# Apollo_ES_Board.net
KiCad netlist of a schematic drawn in Altium Designer
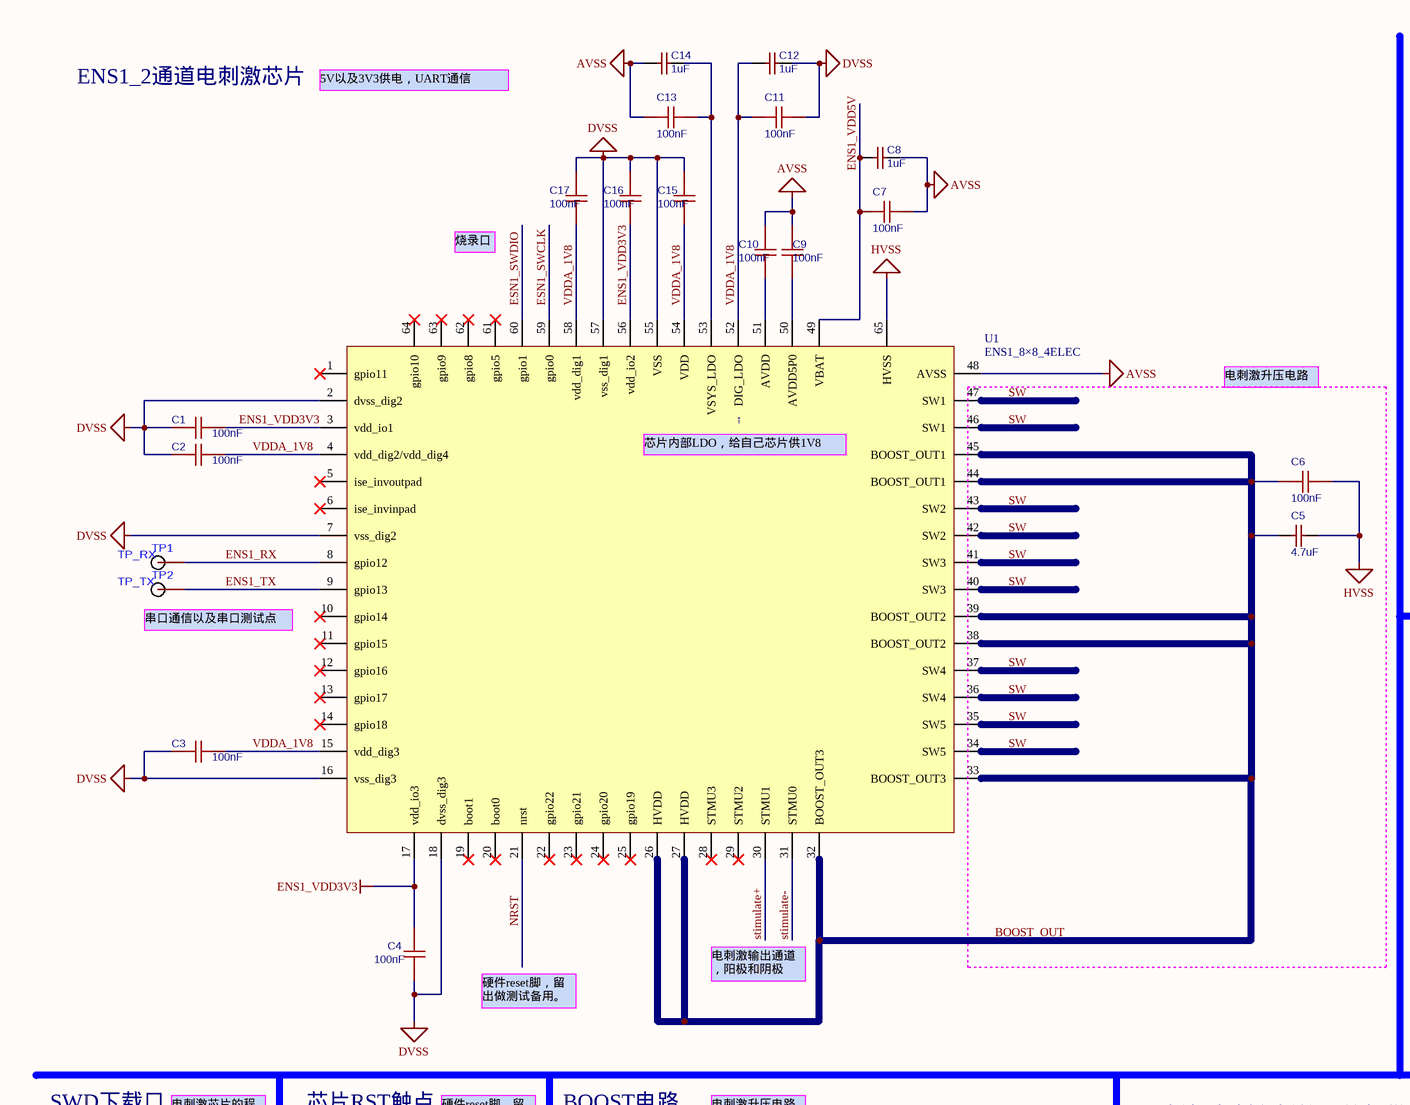
[diagram p0: Apollo_ES_Board.SchDoc, top left]
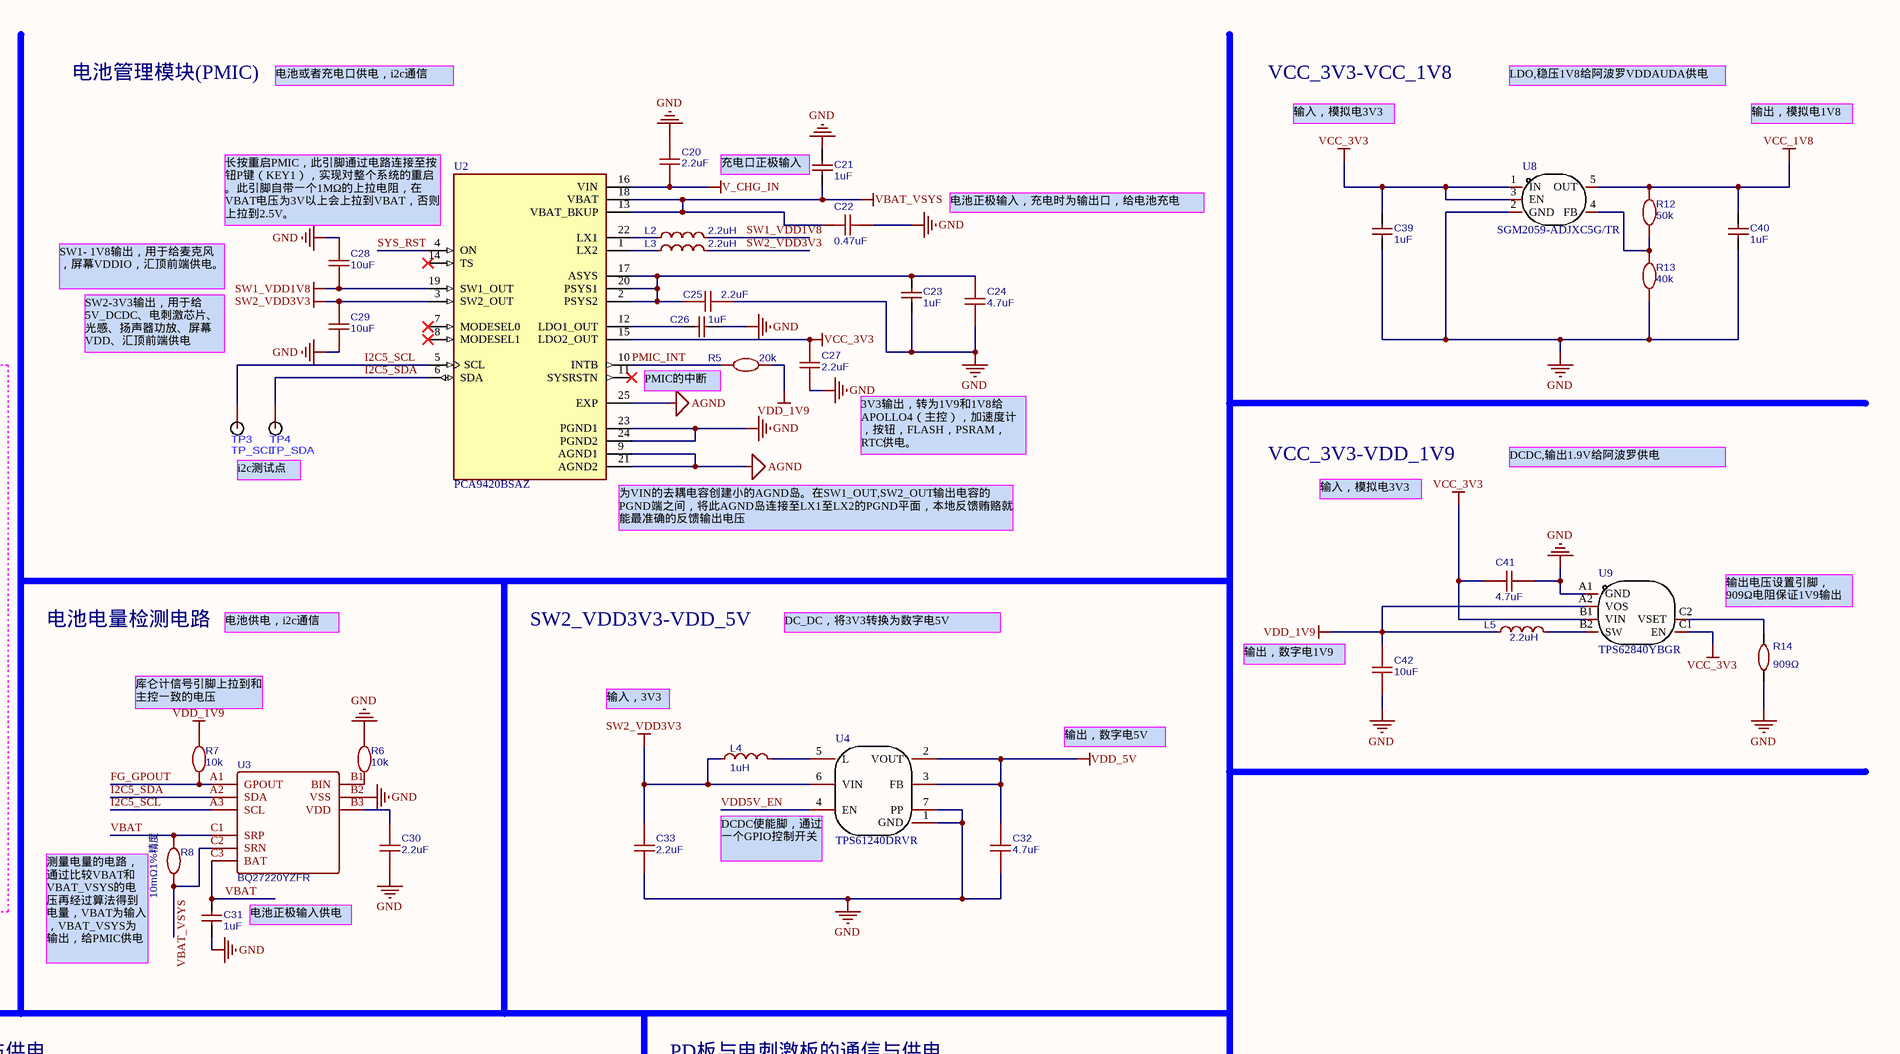
[diagram p1: Apollo_ES_Board.SchDoc, top right]
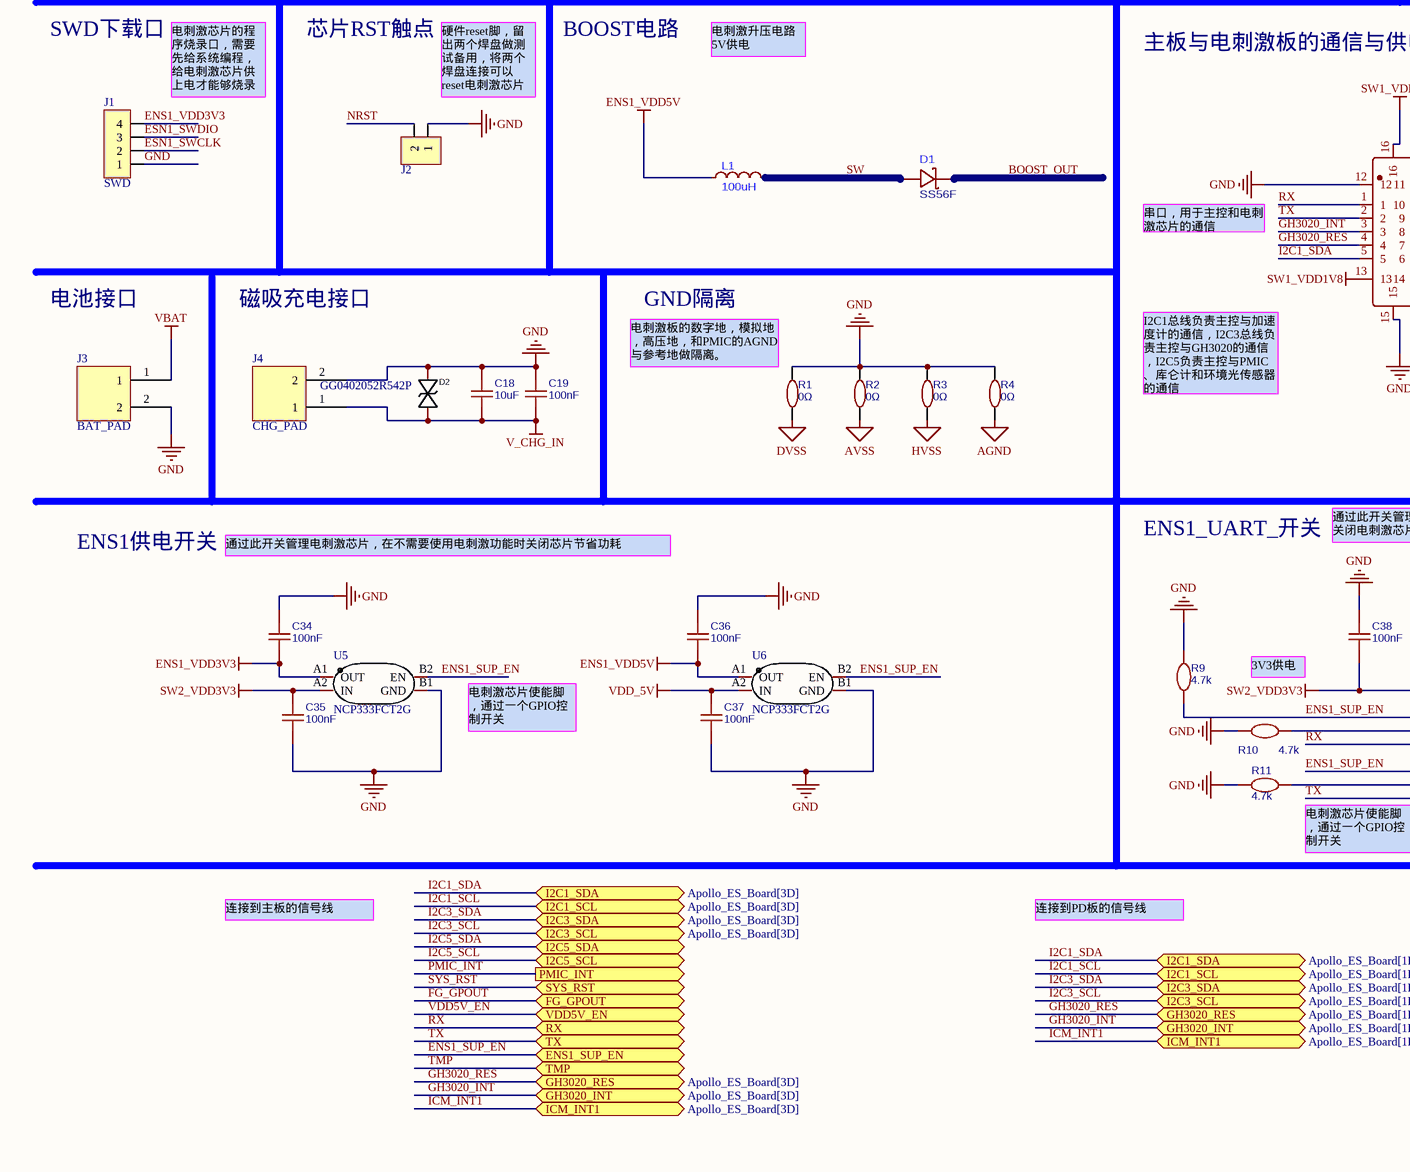
[diagram p2: Apollo_ES_Board.SchDoc, bottom left]
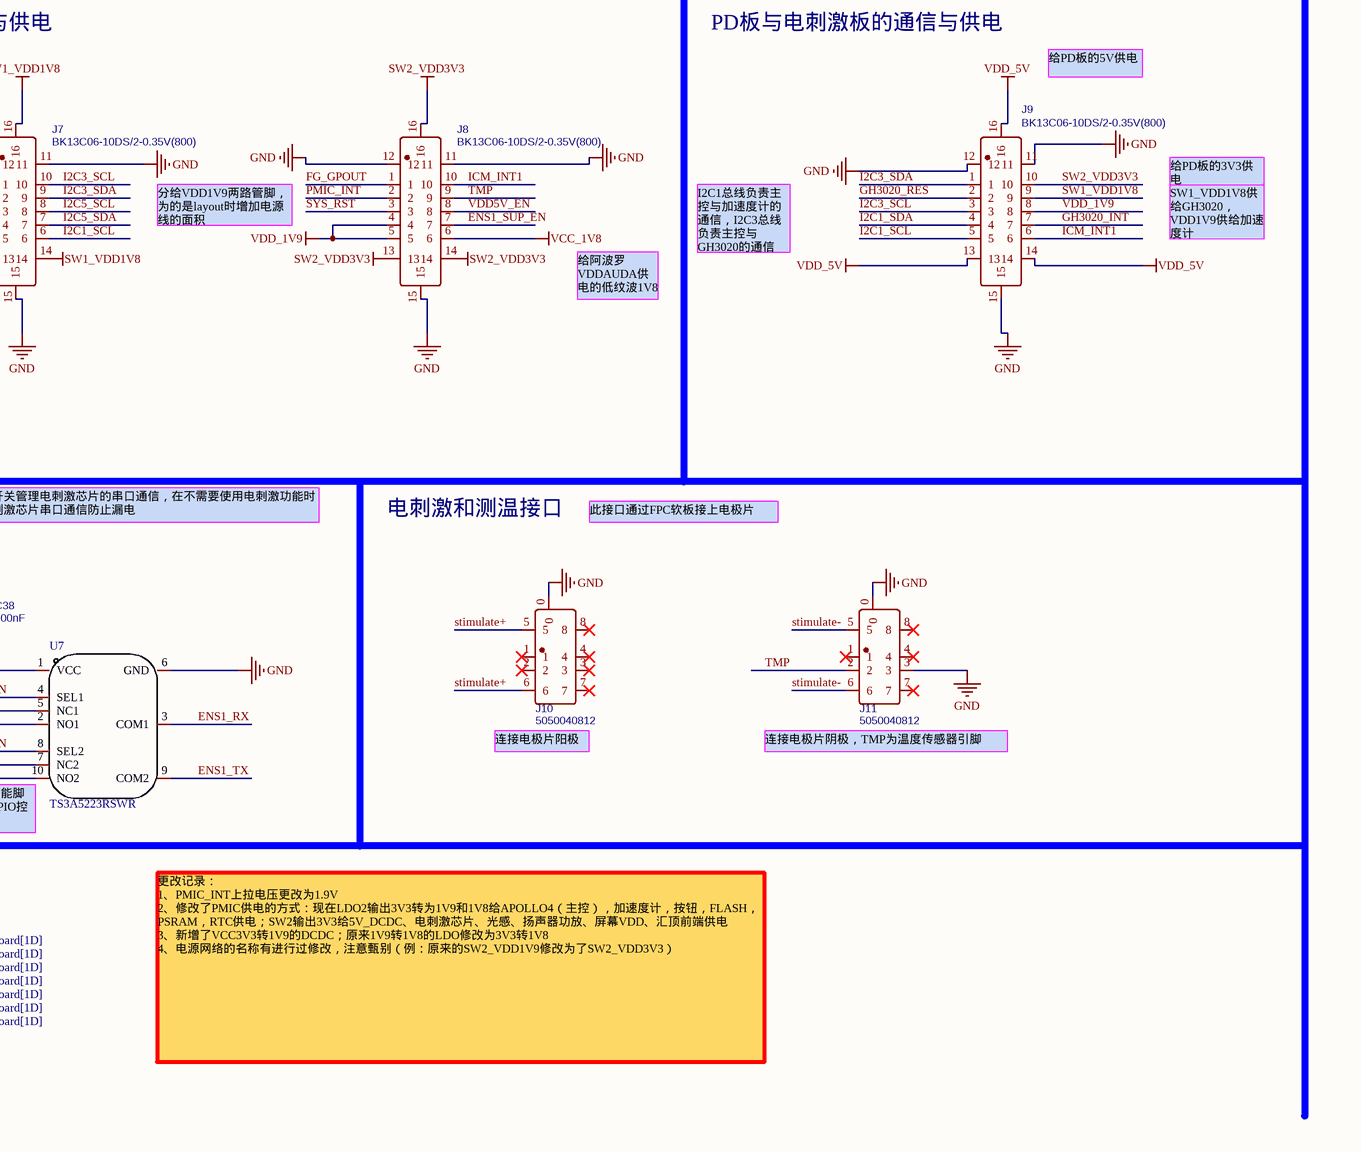
[diagram p3: Apollo_ES_Board.SchDoc, bottom right]

(export (version "E")
  (design (tool "Eeschema 10.0.6"))
  (components
    (comp (ref "C1")
      (value "100nF")
      (footprint "smart bracelet:C0201")
      (description "CL03A104KO3NNNC\r\n额定电压: 16V\r\n材质(温度系数): X5R")
      (fields
        (field (name "BOM_MANUFACTURER PART") "CL10B104KB8NNNC")
        (field (name "BOM_SUPPLIER PART") "C1591")
      )
      (libsource (lib "smart bracelet") (part "100nF"))
    )
    (comp (ref "C2")
      (value "100nF")
      (footprint "smart bracelet:C0201")
      (description "CL03A104KO3NNNC\r\n额定电压: 16V\r\n材质(温度系数): X5R")
      (fields
        (field (name "BOM_MANUFACTURER PART") "CL10B104KB8NNNC")
        (field (name "BOM_SUPPLIER PART") "C1591")
      )
      (libsource (lib "smart bracelet") (part "100nF"))
    )
    (comp (ref "C3")
      (value "100nF")
      (footprint "smart bracelet:C0201")
      (description "CL03A104KO3NNNC\r\n额定电压: 16V\r\n材质(温度系数): X5R")
      (fields
        (field (name "BOM_MANUFACTURER PART") "CL10B104KB8NNNC")
        (field (name "BOM_SUPPLIER PART") "C1591")
      )
      (libsource (lib "smart bracelet") (part "100nF"))
    )
    (comp (ref "C4")
      (value "100nF")
      (footprint "smart bracelet:C0201")
      (description "CL03A104KO3NNNC\r\n额定电压: 16V\r\n材质(温度系数): X5R")
      (fields
        (field (name "BOM_MANUFACTURER PART") "CL10B104KB8NNNC")
        (field (name "BOM_SUPPLIER PART") "C1591")
      )
      (libsource (lib "smart bracelet") (part "100nF"))
    )
    (comp (ref "C5")
      (value "4.7uF")
      (footprint "C1206")
      (fields
        (field (name "BOM_MANUFACTURER PART") "CL10A105KB8NNNC")
        (field (name "BOM_SUPPLIER PART") "C15849")
      )
      (libsource (lib "smart bracelet") (part "1uF"))
    )
    (comp (ref "C6")
      (value "100nF")
      (footprint "smart bracelet:C0805")
      (fields
        (field (name "BOM_MANUFACTURER PART") "CL10B104KB8NNNC")
        (field (name "BOM_SUPPLIER PART") "C1591")
      )
      (libsource (lib "smart bracelet") (part "100nF"))
    )
    (comp (ref "C7")
      (value "100nF")
      (footprint "smart bracelet:C0201")
      (description "CL03A104KO3NNNC\r\n额定电压: 16V\r\n材质(温度系数): X5R")
      (fields
        (field (name "BOM_MANUFACTURER PART") "CL10B104KB8NNNC")
        (field (name "BOM_SUPPLIER PART") "C1591")
      )
      (libsource (lib "smart bracelet") (part "100nF"))
    )
    (comp (ref "C8")
      (value "1uF")
      (footprint "C0201")
      (description "GRM033R61A105ME44D\r\n精度: ±20%\r\n额定电压: 10V\r\n材质(温度系数): X5R")
      (fields
        (field (name "BOM_MANUFACTURER PART") "CL10A105KB8NNNC")
        (field (name "BOM_SUPPLIER PART") "C15849")
      )
      (libsource (lib "smart bracelet") (part "1uF"))
    )
    (comp (ref "C9")
      (value "100nF")
      (footprint "smart bracelet:C0201")
      (description "CL03A104KO3NNNC\r\n额定电压: 16V\r\n材质(温度系数): X5R")
      (fields
        (field (name "BOM_MANUFACTURER PART") "CL10B104KB8NNNC")
        (field (name "BOM_SUPPLIER PART") "C1591")
      )
      (libsource (lib "smart bracelet") (part "100nF"))
    )
    (comp (ref "C10")
      (value "100nF")
      (footprint "smart bracelet:C0201")
      (description "CL03A104KO3NNNC\r\n额定电压: 16V\r\n材质(温度系数): X5R")
      (fields
        (field (name "BOM_MANUFACTURER PART") "CL10B104KB8NNNC")
        (field (name "BOM_SUPPLIER PART") "C1591")
      )
      (libsource (lib "smart bracelet") (part "100nF"))
    )
    (comp (ref "C11")
      (value "100nF")
      (footprint "smart bracelet:C0201")
      (description "CL03A104KO3NNNC\r\n额定电压: 16V\r\n材质(温度系数): X5R")
      (fields
        (field (name "BOM_MANUFACTURER PART") "CL10B104KB8NNNC")
        (field (name "BOM_SUPPLIER PART") "C1591")
      )
      (libsource (lib "smart bracelet") (part "100nF"))
    )
    (comp (ref "C12")
      (value "1uF")
      (footprint "C0201")
      (description "GRM033R61A105ME44D\r\n精度: ±20%\r\n额定电压: 10V\r\n材质(温度系数): X5R")
      (fields
        (field (name "BOM_MANUFACTURER PART") "CL10A105KB8NNNC")
        (field (name "BOM_SUPPLIER PART") "C15849")
      )
      (libsource (lib "smart bracelet") (part "1uF"))
    )
    (comp (ref "C13")
      (value "100nF")
      (footprint "smart bracelet:C0201")
      (description "CL03A104KO3NNNC\r\n额定电压: 16V\r\n材质(温度系数): X5R")
      (fields
        (field (name "BOM_MANUFACTURER PART") "CL10B104KB8NNNC")
        (field (name "BOM_SUPPLIER PART") "C1591")
      )
      (libsource (lib "smart bracelet") (part "100nF"))
    )
    (comp (ref "C14")
      (value "1uF")
      (footprint "C0201")
      (description "GRM033R61A105ME44D\r\n精度: ±20%\r\n额定电压: 10V\r\n材质(温度系数): X5R")
      (fields
        (field (name "BOM_MANUFACTURER PART") "CL10A105KB8NNNC")
        (field (name "BOM_SUPPLIER PART") "C15849")
      )
      (libsource (lib "smart bracelet") (part "1uF"))
    )
    (comp (ref "C15")
      (value "100nF")
      (footprint "smart bracelet:C0201")
      (description "CL03A104KO3NNNC\r\n额定电压: 16V\r\n材质(温度系数): X5R")
      (fields
        (field (name "BOM_MANUFACTURER PART") "CL10B104KB8NNNC")
        (field (name "BOM_SUPPLIER PART") "C1591")
      )
      (libsource (lib "smart bracelet") (part "100nF"))
    )
    (comp (ref "C16")
      (value "100nF")
      (footprint "smart bracelet:C0201")
      (description "CL03A104KO3NNNC\r\n额定电压: 16V\r\n材质(温度系数): X5R")
      (fields
        (field (name "BOM_MANUFACTURER PART") "CL10B104KB8NNNC")
        (field (name "BOM_SUPPLIER PART") "C1591")
      )
      (libsource (lib "smart bracelet") (part "100nF"))
    )
    (comp (ref "C17")
      (value "100nF")
      (footprint "smart bracelet:C0201")
      (description "CL03A104KO3NNNC\r\n额定电压: 16V\r\n材质(温度系数): X5R")
      (fields
        (field (name "BOM_MANUFACTURER PART") "CL10B104KB8NNNC")
        (field (name "BOM_SUPPLIER PART") "C1591")
      )
      (libsource (lib "smart bracelet") (part "100nF"))
    )
    (comp (ref "C18")
      (value "10uF")
      (footprint "smart bracelet:C0402")
      (description "CL05A106MQ5NUNC\r\n精度: ±20%\r\n额定电压: 6.3V\r\n材质(温度系数): X5R")
      (fields
        (field (name "BOM_SUPPLIER PART") "C2932476")
        (field (name "BOM_MANUFACTURER PART") "CL21A106KBYQNNE")
        (field (name "CONTRIBUTOR") "lcsc")
      )
      (libsource (lib "smart bracelet") (part "10uF"))
    )
    (comp (ref "C19")
      (value "100nF")
      (footprint "smart bracelet:C0201")
      (description "CL03A104KO3NNNC\r\n额定电压: 16V\r\n材质(温度系数): X5R")
      (fields
        (field (name "BOM_MANUFACTURER PART") "CL10B104KB8NNNC")
        (field (name "BOM_SUPPLIER PART") "C1591")
      )
      (libsource (lib "smart bracelet") (part "100nF"))
    )
    (comp (ref "C20")
      (value "2.2uF")
      (footprint "smart bracelet:C0201")
      (fields
        (field (name "BOM_SUPPLIER PART") "C913904")
        (field (name "BOM_MANUFACTURER PART") "CL10A225KB8NNNC")
        (field (name "CONTRIBUTOR") "LCSC")
      )
      (libsource (lib "smart bracelet") (part "C0201"))
    )
    (comp (ref "C21")
      (value "1uF")
      (footprint "C0201")
      (description "GRM033R61A105ME44D\r\n精度: ±20%\r\n额定电压: 10V\r\n材质(温度系数): X5R")
      (fields
        (field (name "BOM_MANUFACTURER PART") "CL10A105KB8NNNC")
        (field (name "BOM_SUPPLIER PART") "C15849")
      )
      (libsource (lib "smart bracelet") (part "1uF"))
    )
    (comp (ref "C22")
      (value "0.47uF")
      (footprint "smart bracelet:C0201")
      (fields
        (field (name "BOM_SUPPLIER PART") "C913904")
        (field (name "BOM_MANUFACTURER PART") "CL10A225KB8NNNC")
        (field (name "CONTRIBUTOR") "LCSC")
      )
      (libsource (lib "smart bracelet") (part "C0201"))
    )
    (comp (ref "C23")
      (value "1uF")
      (footprint "C0201")
      (description "GRM033R61A105ME44D\r\n精度: ±20%\r\n额定电压: 10V\r\n材质(温度系数): X5R")
      (fields
        (field (name "BOM_MANUFACTURER PART") "CL10A105KB8NNNC")
        (field (name "BOM_SUPPLIER PART") "C15849")
      )
      (libsource (lib "smart bracelet") (part "1uF"))
    )
    (comp (ref "C24")
      (value "4.7uF")
      (footprint "C0201")
      (fields
        (field (name "BOM_SUPPLIER PART") "C237304")
        (field (name "BOM_MANUFACTURER PART") "GRM31CC72A475KE11L")
        (field (name "CONTRIBUTOR") "LCSC")
      )
      (libsource (lib "smart bracelet") (part "4.7uF"))
    )
    (comp (ref "C25")
      (value "2.2uF")
      (footprint "smart bracelet:C0201")
      (fields
        (field (name "BOM_SUPPLIER PART") "C913904")
        (field (name "BOM_MANUFACTURER PART") "CL10A225KB8NNNC")
        (field (name "CONTRIBUTOR") "LCSC")
      )
      (libsource (lib "smart bracelet") (part "C0201"))
    )
    (comp (ref "C26")
      (value "1uF")
      (footprint "C0201")
      (description "GRM033R61A105ME44D\r\n精度: ±20%\r\n额定电压: 10V\r\n材质(温度系数): X5R")
      (fields
        (field (name "BOM_MANUFACTURER PART") "CL10A105KB8NNNC")
        (field (name "BOM_SUPPLIER PART") "C15849")
      )
      (libsource (lib "smart bracelet") (part "1uF"))
    )
    (comp (ref "C27")
      (value "2.2uF")
      (footprint "smart bracelet:C0201")
      (fields
        (field (name "BOM_SUPPLIER PART") "C913904")
        (field (name "BOM_MANUFACTURER PART") "CL10A225KB8NNNC")
        (field (name "CONTRIBUTOR") "LCSC")
      )
      (libsource (lib "smart bracelet") (part "C0201"))
    )
    (comp (ref "C28")
      (value "10uF")
      (footprint "smart bracelet:C0402")
      (fields
        (field (name "BOM_SUPPLIER PART") "C913904")
        (field (name "BOM_MANUFACTURER PART") "CL10A225KB8NNNC")
        (field (name "CONTRIBUTOR") "LCSC")
      )
      (libsource (lib "smart bracelet") (part "C0402"))
    )
    (comp (ref "C29")
      (value "10uF")
      (footprint "smart bracelet:C0402")
      (fields
        (field (name "BOM_SUPPLIER PART") "C913904")
        (field (name "BOM_MANUFACTURER PART") "CL10A225KB8NNNC")
        (field (name "CONTRIBUTOR") "LCSC")
      )
      (libsource (lib "smart bracelet") (part "C0402"))
    )
    (comp (ref "C30")
      (value "2.2uF")
      (footprint "smart bracelet:C0201")
      (fields
        (field (name "BOM_SUPPLIER PART") "C913904")
        (field (name "BOM_MANUFACTURER PART") "CL10A225KB8NNNC")
        (field (name "CONTRIBUTOR") "LCSC")
      )
      (libsource (lib "smart bracelet") (part "C0201"))
    )
    (comp (ref "C31")
      (value "1uF")
      (footprint "C0201")
      (description "GRM033R61A105ME44D\r\n精度: ±20%\r\n额定电压: 10V\r\n材质(温度系数): X5R")
      (fields
        (field (name "BOM_MANUFACTURER PART") "CL10A105KB8NNNC")
        (field (name "BOM_SUPPLIER PART") "C15849")
      )
      (libsource (lib "smart bracelet") (part "1uF"))
    )
    (comp (ref "C32")
      (value "4.7uF")
      (footprint "C0201")
      (fields
        (field (name "BOM_SUPPLIER PART") "C237304")
        (field (name "BOM_MANUFACTURER PART") "GRM31CC72A475KE11L")
        (field (name "CONTRIBUTOR") "LCSC")
      )
      (libsource (lib "smart bracelet") (part "4.7uF"))
    )
    (comp (ref "C33")
      (value "2.2uF")
      (footprint "smart bracelet:C0201")
      (fields
        (field (name "BOM_SUPPLIER PART") "C913904")
        (field (name "BOM_MANUFACTURER PART") "CL10A225KB8NNNC")
        (field (name "CONTRIBUTOR") "LCSC")
      )
      (libsource (lib "smart bracelet") (part "C0201"))
    )
    (comp (ref "C34")
      (value "100nF")
      (footprint "smart bracelet:C0201")
      (description "CL03A104KO3NNNC\r\n额定电压: 16V\r\n材质(温度系数): X5R")
      (fields
        (field (name "BOM_MANUFACTURER PART") "CL10B104KB8NNNC")
        (field (name "BOM_SUPPLIER PART") "C1591")
      )
      (libsource (lib "smart bracelet") (part "100nF"))
    )
    (comp (ref "C35")
      (value "100nF")
      (footprint "smart bracelet:C0201")
      (description "CL03A104KO3NNNC\r\n额定电压: 16V\r\n材质(温度系数): X5R")
      (fields
        (field (name "BOM_MANUFACTURER PART") "CL10B104KB8NNNC")
        (field (name "BOM_SUPPLIER PART") "C1591")
      )
      (libsource (lib "smart bracelet") (part "100nF"))
    )
    (comp (ref "C36")
      (value "100nF")
      (footprint "smart bracelet:C0201")
      (description "CL03A104KO3NNNC\r\n额定电压: 16V\r\n材质(温度系数): X5R")
      (fields
        (field (name "BOM_MANUFACTURER PART") "CL10B104KB8NNNC")
        (field (name "BOM_SUPPLIER PART") "C1591")
      )
      (libsource (lib "smart bracelet") (part "100nF"))
    )
    (comp (ref "C37")
      (value "100nF")
      (footprint "smart bracelet:C0201")
      (description "CL03A104KO3NNNC\r\n额定电压: 16V\r\n材质(温度系数): X5R")
      (fields
        (field (name "BOM_MANUFACTURER PART") "CL10B104KB8NNNC")
        (field (name "BOM_SUPPLIER PART") "C1591")
      )
      (libsource (lib "smart bracelet") (part "100nF"))
    )
    (comp (ref "C38")
      (value "100nF")
      (footprint "smart bracelet:C0201")
      (description "CL03A104KO3NNNC\r\n额定电压: 16V\r\n材质(温度系数): X5R")
      (fields
        (field (name "BOM_MANUFACTURER PART") "CL10B104KB8NNNC")
        (field (name "BOM_SUPPLIER PART") "C1591")
      )
      (libsource (lib "smart bracelet") (part "100nF"))
    )
    (comp (ref "C39")
      (value "1uF")
      (footprint "C0201")
      (description "GRM033R61A105ME44D\r\n精度: ±20%\r\n额定电压: 10V\r\n材质(温度系数): X5R")
      (fields
        (field (name "BOM_MANUFACTURER PART") "CL10A105KB8NNNC")
        (field (name "BOM_SUPPLIER PART") "C15849")
      )
      (libsource (lib "smart bracelet") (part "1uF"))
    )
    (comp (ref "C40")
      (value "1uF")
      (footprint "C0201")
      (description "GRM033R61A105ME44D\r\n精度: ±20%\r\n额定电压: 10V\r\n材质(温度系数): X5R")
      (fields
        (field (name "BOM_MANUFACTURER PART") "CL10A105KB8NNNC")
        (field (name "BOM_SUPPLIER PART") "C15849")
      )
      (libsource (lib "smart bracelet") (part "1uF"))
    )
    (comp (ref "C41")
      (value "4.7uF")
      (footprint "C0201")
      (fields
        (field (name "BOM_SUPPLIER PART") "C237304")
        (field (name "BOM_MANUFACTURER PART") "GRM31CC72A475KE11L")
        (field (name "CONTRIBUTOR") "LCSC")
      )
      (libsource (lib "smart bracelet") (part "4.7uF"))
    )
    (comp (ref "C42")
      (value "10uF")
      (footprint "smart bracelet:C0402")
      (fields
        (field (name "BOM_SUPPLIER PART") "C913904")
        (field (name "BOM_MANUFACTURER PART") "CL10A225KB8NNNC")
        (field (name "CONTRIBUTOR") "LCSC")
      )
      (libsource (lib "smart bracelet") (part "C0402"))
    )
    (comp (ref "D1")
      (value "SS56F")
      (footprint "SMAF_L3.5-W2.6-LS4.7-RD")
      (libsource (lib "altium-import") (part "root_2_SS56F_"))
    )
    (comp (ref "D2")
      (value "GG0402052R542P")
      (footprint "smart bracelet:0402")
      (fields (field (name "MANUFACTURER") "Kyocera AVX"))
      (libsource (lib "smart bracelet") (part "GG0402052R542P"))
    )
    (comp (ref "J1")
      (value "SWD")
      (footprint "4PIN_1.27mm")
      (description "Header, 4-Pin")
      (fields (field (name "PUBLISHER") "Altium Limited"))
      (libsource (lib "smart bracelet") (part "Header 4"))
    )
    (comp (ref "J2")
      (value "~")
      (footprint "2PIN_1.27mm")
      (description "Header, 2-Pin, encryption interface")
      (fields (field (name "PUBLISHER") "Altium Limited"))
      (libsource (lib "smart bracelet") (part "Header 2"))
    )
    (comp (ref "J3")
      (value "BAT_PAD")
      (footprint "MOTOR_PAD")
      (libsource (lib "smart bracelet") (part "MOTOR_PAD"))
    )
    (comp (ref "J4")
      (value "CHG_PAD")
      (footprint "CHG_PAD")
      (libsource (lib "smart bracelet") (part "CHG_PAD"))
    )
    (comp (ref "J7")
      (value "BK13C06-10DS/2-0.35V(800)")
      (footprint "smart bracelet:CONN-SMD_BK13C06-10DS-2-0.35V-800")
      (fields (field (name "MANUFACTURER") "HRS(广濑)") (field (name "CONTRIBUTOR") "lcsc"))
      (libsource (lib "smart bracelet") (part "10pin_ds_BK13C06-10DS/2-0.35V(800)"))
    )
    (comp (ref "J8")
      (value "BK13C06-10DS/2-0.35V(800)")
      (footprint "smart bracelet:CONN-SMD_BK13C06-10DS-2-0.35V-800")
      (fields (field (name "MANUFACTURER") "HRS(广濑)") (field (name "CONTRIBUTOR") "lcsc"))
      (libsource (lib "smart bracelet") (part "10pin_ds_BK13C06-10DS/2-0.35V(800)"))
    )
    (comp (ref "J9")
      (value "BK13C06-10DS/2-0.35V(800)")
      (footprint "smart bracelet:CONN-SMD_BK13C06-10DS-2-0.35V-800")
      (fields (field (name "MANUFACTURER") "HRS(广濑)") (field (name "CONTRIBUTOR") "lcsc"))
      (libsource (lib "Copy of smart bracelet") (part "10pin_ds_BK13C06-10DS/2-0.35V(800)"))
    )
    (comp (ref "J10")
      (value "5050040812")
      (footprint "smart bracelet:CONN-SMD_4P-P0.40_5050040812")
      (fields (field (name "MANUFACTURER") "MOLEX") (field (name "CONTRIBUTOR") "lcsc"))
      (libsource (lib "smart bracelet") (part "5050040812_8pin_ds"))
    )
    (comp (ref "J11")
      (value "5050040812")
      (footprint "smart bracelet:CONN-SMD_4P-P0.40_5050040812")
      (fields (field (name "MANUFACTURER") "MOLEX") (field (name "CONTRIBUTOR") "lcsc"))
      (libsource (lib "smart bracelet") (part "5050040812_8pin_ds"))
    )
    (comp (ref "L1")
      (value "100uH")
      (footprint "IND-SMD_L3.0-W3.0_SMNR3015")
      (description "XRNR3015-100uH，±20%")
      (libsource (lib "smart bracelet") (part "YNR6045-101M"))
    )
    (comp (ref "L2")
      (value "2.2uH")
      (footprint "smart bracelet:L0805")
      (fields
        (field (name "MANUFACTURER") "cjiang(长江微电)")
        (field (name "MANUFACTURER PART") "FNR252010S1R0NT")
        (field (name "CONTRIBUTOR") "LCSC")
      )
      (libsource (lib "smart bracelet") (part "1uH_1.8A"))
    )
    (comp (ref "L3")
      (value "2.2uH")
      (footprint "smart bracelet:L0805")
      (fields
        (field (name "MANUFACTURER") "cjiang(长江微电)")
        (field (name "MANUFACTURER PART") "FNR252010S1R0NT")
        (field (name "CONTRIBUTOR") "LCSC")
      )
      (libsource (lib "smart bracelet") (part "1uH_1.8A"))
    )
    (comp (ref "L4")
      (value "1uH")
      (footprint "smart bracelet:IND-SMD_L2.5-W2.0_FNR252012S")
      (fields
        (field (name "MANUFACTURER") "cjiang(长江微电)")
        (field (name "MANUFACTURER PART") "FNR252010S1R0NT")
        (field (name "CONTRIBUTOR") "LCSC")
      )
      (libsource (lib "smart bracelet") (part "1uH_1.8A"))
    )
    (comp (ref "L5")
      (value "2.2uH")
      (footprint "smart bracelet:C0603")
      (fields
        (field (name "MANUFACTURER") "cjiang(长江微电)")
        (field (name "MANUFACTURER PART") "FNR252010S1R0NT")
        (field (name "CONTRIBUTOR") "LCSC")
      )
      (libsource (lib "smart bracelet") (part "1uH_1.8A"))
    )
    (comp (ref "R1")
      (value "0Ω")
      (footprint "smart bracelet:0402")
      (description "FRC0402F0000TS，±1%")
      (fields
        (field (name "BOM_MANUFACTURER PART") "ERJ3GEY0R00V")
        (field (name "BOM_SUPPLIER PART") "C122704")
      )
      (libsource (lib "smart bracelet") (part "0Ω"))
    )
    (comp (ref "R2")
      (value "0Ω")
      (footprint "smart bracelet:0402")
      (description "FRC0402F0000TS，±1%")
      (fields
        (field (name "BOM_MANUFACTURER PART") "ERJ3GEY0R00V")
        (field (name "BOM_SUPPLIER PART") "C122704")
      )
      (libsource (lib "smart bracelet") (part "0Ω"))
    )
    (comp (ref "R3")
      (value "0Ω")
      (footprint "C0603")
      (description "0603WAF0000T5E，±1%，100mW，最大工作电压75V")
      (fields
        (field (name "BOM_MANUFACTURER PART") "ERJ3GEY0R00V")
        (field (name "BOM_SUPPLIER PART") "C122704")
      )
      (libsource (lib "smart bracelet") (part "0Ω"))
    )
    (comp (ref "R4")
      (value "0Ω")
      (footprint "smart bracelet:0402")
      (description "FRC0402F0000TS，±1%")
      (fields
        (field (name "BOM_MANUFACTURER PART") "ERJ3GEY0R00V")
        (field (name "BOM_SUPPLIER PART") "C122704")
      )
      (libsource (lib "smart bracelet") (part "0Ω"))
    )
    (comp (ref "R5")
      (value "20k")
      (footprint "smart bracelet:RES0201")
      (description "0201WMF2002TEE\r\n品牌: UNI-ROYAL(厚声)\r\n封装: 0201\r\n电阻类型: 厚膜电阻\r\n阻值: 20kΩ\r\n精度: ±1%\r\n功率: 50mW")
      (fields
        (field (name "BOM_SUPPLIER PART") "C2989113")
        (field (name "BOM_MANUFACTURER PART") "TC0325B1000T5F")
        (field (name "CONTRIBUTOR") "lcsc")
      )
      (libsource (lib "smart bracelet") (part "RES0402"))
    )
    (comp (ref "R6")
      (value "10k")
      (footprint "smart bracelet:RES0201")
      (description "0201WMF1002TEE\r\n品牌: UNI-ROYAL(厚声)\r\n封装: 0201\r\n电阻类型: 厚膜电阻\r\n阻值: 10kΩ\r\n精度: ±1%\r\n功率: 50mW")
      (fields
        (field (name "BOM_SUPPLIER PART") "C2989113")
        (field (name "BOM_MANUFACTURER PART") "TC0325B1000T5F")
        (field (name "CONTRIBUTOR") "lcsc")
      )
      (libsource (lib "smart bracelet") (part "RES0201"))
    )
    (comp (ref "R7")
      (value "10k")
      (footprint "smart bracelet:RES0201")
      (description "0201WMF1002TEE\r\n品牌: UNI-ROYAL(厚声)\r\n封装: 0201\r\n电阻类型: 厚膜电阻\r\n阻值: 10kΩ\r\n精度: ±1%\r\n功率: 50mW")
      (fields
        (field (name "BOM_SUPPLIER PART") "C2989113")
        (field (name "BOM_MANUFACTURER PART") "TC0325B1000T5F")
        (field (name "CONTRIBUTOR") "lcsc")
      )
      (libsource (lib "smart bracelet") (part "RES0201"))
    )
    (comp (ref "R8")
      (value "10mΩ1%精度")
      (footprint "smart bracelet:0402")
      (description "品牌: Milliohm(毫欧)\r\n封装: 0402\r\n电阻类型: 陶瓷电阻\r\n阻值: 10mΩ\r\n精度: ±1%\r\n功率: 250mW")
      (fields
        (field (name "BOM_SUPPLIER PART") "C2989113")
        (field (name "BOM_MANUFACTURER PART") "TC0325B1000T5F")
        (field (name "CONTRIBUTOR") "lcsc")
      )
      (libsource (lib "smart bracelet") (part "RES0402"))
    )
    (comp (ref "R9")
      (value "4.7k")
      (footprint "smart bracelet:RES0201")
      (description "0201WMF4701TEE\r\n品牌: UNI-ROYAL(厚声)\r\n封装: 0201\r\n电阻类型: 厚膜电阻\r\n阻值: 4.7kΩ\r\n精度: ±1%\r\n功率: 50mW")
      (fields
        (field (name "BOM_SUPPLIER PART") "C2989113")
        (field (name "BOM_MANUFACTURER PART") "TC0325B1000T5F")
        (field (name "CONTRIBUTOR") "lcsc")
      )
      (libsource (lib "smart bracelet") (part "RES0201"))
    )
    (comp (ref "R10")
      (value "4.7k")
      (footprint "smart bracelet:RES0201")
      (description "0201WMF4701TEE\r\n品牌: UNI-ROYAL(厚声)\r\n封装: 0201\r\n电阻类型: 厚膜电阻\r\n阻值: 4.7kΩ\r\n精度: ±1%\r\n功率: 50mW")
      (fields
        (field (name "BOM_SUPPLIER PART") "C2989113")
        (field (name "BOM_MANUFACTURER PART") "TC0325B1000T5F")
        (field (name "CONTRIBUTOR") "lcsc")
      )
      (libsource (lib "smart bracelet") (part "RES0201"))
    )
    (comp (ref "R11")
      (value "4.7k")
      (footprint "smart bracelet:RES0201")
      (description "0201WMF4701TEE\r\n品牌: UNI-ROYAL(厚声)\r\n封装: 0201\r\n电阻类型: 厚膜电阻\r\n阻值: 4.7kΩ\r\n精度: ±1%\r\n功率: 50mW")
      (fields
        (field (name "BOM_SUPPLIER PART") "C2989113")
        (field (name "BOM_MANUFACTURER PART") "TC0325B1000T5F")
        (field (name "CONTRIBUTOR") "lcsc")
      )
      (libsource (lib "smart bracelet") (part "RES0201"))
    )
    (comp (ref "R12")
      (value "50k")
      (footprint "smart bracelet:C0603")
      (fields
        (field (name "BOM_SUPPLIER PART") "C2989113")
        (field (name "BOM_MANUFACTURER PART") "TC0325B1000T5F")
        (field (name "CONTRIBUTOR") "lcsc")
      )
      (libsource (lib "smart bracelet") (part "RES0201"))
    )
    (comp (ref "R13")
      (value "40k")
      (footprint "smart bracelet:C0603")
      (description "SCR0603F40K\r\n品牌: VO(翔胜)\r\n封装: 0603\r\n电阻类型: 厚膜电阻\r\n阻值: 40kΩ\r\n精度: ±1%\r\n功率: 100mW")
      (fields
        (field (name "BOM_SUPPLIER PART") "C2989113")
        (field (name "BOM_MANUFACTURER PART") "TC0325B1000T5F")
        (field (name "CONTRIBUTOR") "lcsc")
      )
      (libsource (lib "smart bracelet") (part "RES0201"))
    )
    (comp (ref "R14")
      (value "909Ω")
      (footprint "smart bracelet:0402")
      (description "FRC0402F9090TS\r\n品牌: FOJAN(富捷)\r\n封装: 0402\r\n电阻类型: 厚膜电阻\r\n阻值: 909Ω\r\n精度: ±1%\r\n功率: 62.5mW")
      (fields
        (field (name "BOM_MANUFACTURER PART") "ERJ3GEY0R00V")
        (field (name "BOM_SUPPLIER PART") "C122704")
      )
      (libsource (lib "smart bracelet") (part "0Ω"))
    )
    (comp (ref "TP1") (value "TP_RX") (footprint "Testpoint") (libsource (lib "smart bracelet") (part "TP")))
    (comp (ref "TP2") (value "TP_TX") (footprint "Testpoint") (libsource (lib "smart bracelet") (part "TP")))
    (comp (ref "TP3") (value "TP_SCL") (footprint "Testpoint") (libsource (lib "smart bracelet") (part "TP")))
    (comp (ref "TP4") (value "TP_SDA") (footprint "Testpoint") (libsource (lib "smart bracelet") (part "TP")))
    (comp (ref "U1")
      (value "ENS1_8×8_4ELEC")
      (footprint "QFN64P800X800X90_HS-65L")
      (libsource (lib "ES001A2_EVM_Project") (part "ENS1_8×8_4ELEC"))
    )
    (comp (ref "U2")
      (value "PCA9420BSAZ")
      (footprint "smart bracelet:IC_PCA9420BSAZ")
      (description "Power Management IC 3.3V to 5.5V 24-Pin HVQFN EP T/R")
      (fields (field (name "MF") "NXP Semiconductors"))
      (libsource (lib "smart bracelet") (part "PCA9420BSAZ"))
    )
    (comp (ref "U3")
      (value "BQ27220YZFR")
      (footprint "smart bracelet:DSBGA-9_L1.7-W1.6-R3-C3-P0.50-BL")
      (fields (field (name "MANUFACTURER") "TI(德州仪器)") (field (name "CONTRIBUTOR") "LCSC"))
      (libsource (lib "smart bracelet") (part "BQ27220YZFR"))
    )
    (comp (ref "U4")
      (value "TPS61240DRVR")
      (footprint "WSON-6_L2.0-W2.0-P0.65-TL-EP")
      (fields (field (name "MANUFACTURER") "TI(德州仪器)") (field (name "NAME") "TPS61240DRVR"))
      (libsource (lib "smart bracelet") (part "TPS61240DRVR"))
    )
    (comp (ref "U5")
      (value "NCP333FCT2G")
      (footprint "WLCSP-4_L0.8-W0.8-R2-C2-P0.40-BL")
      (fields (field (name "MANUFACTURER") "onsemi(安森美)") (field (name "NAME") "NCP333FCT2G"))
      (libsource (lib "smart bracelet") (part "NCP333FCT2G"))
    )
    (comp (ref "U6")
      (value "NCP333FCT2G")
      (footprint "WLCSP-4_L0.8-W0.8-R2-C2-P0.40-BL")
      (fields (field (name "MANUFACTURER") "onsemi(安森美)") (field (name "NAME") "NCP333FCT2G"))
      (libsource (lib "smart bracelet") (part "NCP333FCT2G"))
    )
    (comp (ref "U7")
      (value "TS3A5223RSWR")
      (footprint "QFN-10_L1.4-W1.8-P0.40-BL")
      (fields (field (name "MANUFACTURER") "TI(德州仪器)") (field (name "NAME") "TS3A5223RSWR"))
      (libsource (lib "smart bracelet") (part "TS3A5223RSWR"))
    )
    (comp (ref "U8")
      (value "SGM2059-ADJXC5G/TR")
      (footprint "SC-70-5_L2.1-W1.3-P0.65-LS2.2-BR")
      (fields (field (name "MANUFACTURER") "SGMICRO(圣邦微)") (field (name "NAME") "SGM2059-ADJXC5G/TR"))
      (libsource (lib "smart bracelet") (part "SGM2059-ADJXC5G/TR"))
    )
    (comp (ref "U9")
      (value "TPS62840YBGR")
      (footprint "DSBGA-6_L1.4-W1.0-R2-C3-P0.40-BL")
      (fields (field (name "MANUFACTURER") "TI(德州仪器)") (field (name "NAME") "TPS62840YBGR"))
      (libsource (lib "smart bracelet") (part "TPS62840YBGR"))
    )
  )
  (nets
    (net (code "1") (name "/BOOST_OUT") (class "Default")
      (node (ref "C5") (pin "1") (pinfunction "1_1") (pintype "passive"))
      (node (ref "C6") (pin "1") (pinfunction "1_1") (pintype "passive"))
      (node (ref "D1") (pin "1") (pinfunction "K_1") (pintype "passive"))
      (node (ref "U1") (pin "26") (pinfunction "HVDD_26") (pintype "passive"))
      (node (ref "U1") (pin "27") (pinfunction "HVDD_27") (pintype "passive"))
      (node (ref "U1") (pin "32") (pinfunction "BOOST_OUT3_32") (pintype "passive"))
      (node (ref "U1") (pin "33") (pinfunction "BOOST_OUT3_33") (pintype "passive"))
      (node (ref "U1") (pin "38") (pinfunction "BOOST_OUT2_38") (pintype "passive"))
      (node (ref "U1") (pin "39") (pinfunction "BOOST_OUT2_39") (pintype "passive"))
      (node (ref "U1") (pin "44") (pinfunction "BOOST_OUT1_44") (pintype "passive"))
      (node (ref "U1") (pin "45") (pinfunction "BOOST_OUT1_45") (pintype "passive"))
    )
    (net (code "2") (name "/ENS1_RX") (class "Default")
      (node (ref "TP1") (pin "1") (pinfunction "text_1") (pintype "passive"))
      (node (ref "U1") (pin "8") (pinfunction "gpio12_8") (pintype "passive"))
      (node (ref "U7") (pin "3") (pinfunction "COM1_3") (pintype "passive"))
    )
    (net (code "3") (name "/ENS1_SUP_EN") (class "Default")
      (node (ref "J8") (pin "7") (pinfunction "7_7") (pintype "passive"))
      (node (ref "R9") (pin "2") (pinfunction "2_2") (pintype "passive"))
      (node (ref "U5") (pin "B2") (pinfunction "EN_B2") (pintype "passive"))
      (node (ref "U6") (pin "B2") (pinfunction "EN_B2") (pintype "passive"))
      (node (ref "U7") (pin "4") (pinfunction "SEL1_4") (pintype "passive"))
      (node (ref "U7") (pin "8") (pinfunction "SEL2_8") (pintype "passive"))
    )
    (net (code "4") (name "/ENS1_TX") (class "Default")
      (node (ref "TP2") (pin "1") (pinfunction "text_1") (pintype "passive"))
      (node (ref "U1") (pin "9") (pinfunction "gpio13_9") (pintype "passive"))
      (node (ref "U7") (pin "9") (pinfunction "COM2_9") (pintype "passive"))
    )
    (net (code "5") (name "/ESN1_SWCLK") (class "Default")
      (node (ref "J1") (pin "2") (pinfunction "2_2") (pintype "passive"))
      (node (ref "U1") (pin "59") (pinfunction "gpio0_59") (pintype "passive"))
    )
    (net (code "6") (name "/ESN1_SWDIO") (class "Default")
      (node (ref "J1") (pin "3") (pinfunction "3_3") (pintype "passive"))
      (node (ref "U1") (pin "60") (pinfunction "gpio1_60") (pintype "passive"))
    )
    (net (code "7") (name "/FG_GPOUT") (class "Default")
      (node (ref "J8") (pin "1") (pinfunction "1_1") (pintype "passive"))
      (node (ref "R7") (pin "1") (pinfunction "1_1") (pintype "passive"))
      (node (ref "U3") (pin "A1") (pinfunction "GPOUT_A1") (pintype "passive"))
    )
    (net (code "8") (name "/GH3020_INT") (class "Default")
      (node (ref "J7") (pin "3") (pinfunction "3_3") (pintype "passive"))
      (node (ref "J9") (pin "7") (pinfunction "7_7") (pintype "passive"))
    )
    (net (code "9") (name "/GH3020_RES") (class "Default")
      (node (ref "J7") (pin "4") (pinfunction "4_4") (pintype "passive"))
      (node (ref "J9") (pin "2") (pinfunction "2_2") (pintype "passive"))
    )
    (net (code "10") (name "/I2C1_SCL") (class "Default")
      (node (ref "J7") (pin "6") (pinfunction "6_6") (pintype "passive"))
      (node (ref "J9") (pin "5") (pinfunction "5_5") (pintype "passive"))
    )
    (net (code "11") (name "/I2C1_SDA") (class "Default")
      (node (ref "J7") (pin "5") (pinfunction "5_5") (pintype "passive"))
      (node (ref "J9") (pin "4") (pinfunction "4_4") (pintype "passive"))
    )
    (net (code "12") (name "/I2C3_SCL") (class "Default")
      (node (ref "J7") (pin "10") (pinfunction "10_10") (pintype "passive"))
      (node (ref "J9") (pin "3") (pinfunction "3_3") (pintype "passive"))
    )
    (net (code "13") (name "/I2C3_SDA") (class "Default")
      (node (ref "J7") (pin "9") (pinfunction "9_9") (pintype "passive"))
      (node (ref "J9") (pin "1") (pinfunction "1_1") (pintype "passive"))
    )
    (net (code "14") (name "/I2C5_SCL") (class "Default")
      (node (ref "J7") (pin "8") (pinfunction "8_8") (pintype "passive"))
      (node (ref "TP3") (pin "1") (pinfunction "text_1") (pintype "passive"))
      (node (ref "U2") (pin "5") (pinfunction "SCL_5") (pintype "input"))
      (node (ref "U3") (pin "A3") (pinfunction "SCL_A3") (pintype "passive"))
    )
    (net (code "15") (name "/I2C5_SDA") (class "Default")
      (node (ref "J7") (pin "7") (pinfunction "7_7") (pintype "passive"))
      (node (ref "TP4") (pin "1") (pinfunction "text_1") (pintype "passive"))
      (node (ref "U2") (pin "6") (pinfunction "SDA_6") (pintype "bidirectional"))
      (node (ref "U3") (pin "A2") (pinfunction "SDA_A2") (pintype "passive"))
    )
    (net (code "16") (name "/ICM_INT1") (class "Default")
      (node (ref "J8") (pin "10") (pinfunction "10_10") (pintype "passive"))
      (node (ref "J9") (pin "6") (pinfunction "6_6") (pintype "passive"))
    )
    (net (code "17") (name "/NRST") (class "Default")
      (node (ref "J2") (pin "2") (pinfunction "2_2") (pintype "passive"))
      (node (ref "U1") (pin "21") (pinfunction "nrst_21") (pintype "passive"))
    )
    (net (code "18") (name "/PMIC_INT") (class "Default")
      (node (ref "J8") (pin "2") (pinfunction "2_2") (pintype "passive"))
      (node (ref "R5") (pin "1") (pinfunction "1_1") (pintype "passive"))
      (node (ref "U2") (pin "10") (pinfunction "INTB_10") (pintype "output"))
    )
    (net (code "19") (name "/RX") (class "Default")
      (node (ref "J7") (pin "1") (pinfunction "1_1") (pintype "passive"))
      (node (ref "U7") (pin "2") (pinfunction "NO1_2") (pintype "passive"))
    )
    (net (code "20") (name "/SW") (class "Default")
      (node (ref "D1") (pin "2") (pinfunction "A_2") (pintype "passive"))
      (node (ref "L1") (pin "2") (pinfunction "2_2") (pintype "passive"))
      (node (ref "U1") (pin "34") (pinfunction "SW5_34") (pintype "passive"))
      (node (ref "U1") (pin "35") (pinfunction "SW5_35") (pintype "passive"))
      (node (ref "U1") (pin "36") (pinfunction "SW4_36") (pintype "passive"))
      (node (ref "U1") (pin "37") (pinfunction "SW4_37") (pintype "passive"))
      (node (ref "U1") (pin "40") (pinfunction "SW3_40") (pintype "passive"))
      (node (ref "U1") (pin "41") (pinfunction "SW3_41") (pintype "passive"))
      (node (ref "U1") (pin "42") (pinfunction "SW2_42") (pintype "passive"))
      (node (ref "U1") (pin "43") (pinfunction "SW2_43") (pintype "passive"))
      (node (ref "U1") (pin "46") (pinfunction "SW1_46") (pintype "passive"))
      (node (ref "U1") (pin "47") (pinfunction "SW1_47") (pintype "passive"))
    )
    (net (code "21") (name "/SYS_RST") (class "Default")
      (node (ref "J8") (pin "3") (pinfunction "3_3") (pintype "passive"))
      (node (ref "U2") (pin "4") (pinfunction "ON_4") (pintype "input"))
    )
    (net (code "22") (name "/TMP") (class "Default")
      (node (ref "J11") (pin "2") (pinfunction "2_2") (pintype "passive"))
      (node (ref "J8") (pin "9") (pinfunction "9_9") (pintype "passive"))
    )
    (net (code "23") (name "/TX") (class "Default")
      (node (ref "J7") (pin "2") (pinfunction "2_2") (pintype "passive"))
      (node (ref "U7") (pin "10") (pinfunction "NO2_10") (pintype "passive"))
    )
    (net (code "24") (name "/VDD5V_EN") (class "Default")
      (node (ref "J8") (pin "8") (pinfunction "8_8") (pintype "passive"))
      (node (ref "U4") (pin "4") (pinfunction "EN_4") (pintype "passive"))
    )
    (net (code "25") (name "/VDDA_1V8") (class "Default")
      (node (ref "C11") (pin "1") (pinfunction "1_1") (pintype "passive"))
      (node (ref "C12") (pin "2") (pinfunction "2_2") (pintype "passive"))
      (node (ref "C15") (pin "1") (pinfunction "1_1") (pintype "passive"))
      (node (ref "C17") (pin "1") (pinfunction "1_1") (pintype "passive"))
      (node (ref "C2") (pin "1") (pinfunction "1_1") (pintype "passive"))
      (node (ref "C3") (pin "1") (pinfunction "1_1") (pintype "passive"))
      (node (ref "U1") (pin "15") (pinfunction "vdd_dig3_15") (pintype "passive"))
      (node (ref "U1") (pin "4") (pinfunction "vdd_dig2/vdd_dig4_4") (pintype "passive"))
      (node (ref "U1") (pin "52") (pinfunction "DIG_LDO_52") (pintype "passive"))
      (node (ref "U1") (pin "54") (pinfunction "VDD_54") (pintype "passive"))
      (node (ref "U1") (pin "58") (pinfunction "vdd_dig1_58") (pintype "passive"))
    )
    (net (code "26") (name "/stimulate+") (class "Default")
      (node (ref "J10") (pin "5") (pinfunction "5_5") (pintype "passive"))
      (node (ref "J10") (pin "6") (pinfunction "6_6") (pintype "passive"))
      (node (ref "U1") (pin "30") (pinfunction "STMU1_30") (pintype "passive"))
    )
    (net (code "27") (name "/stimulate-") (class "Default")
      (node (ref "J11") (pin "5") (pinfunction "5_5") (pintype "passive"))
      (node (ref "J11") (pin "6") (pinfunction "6_6") (pintype "passive"))
      (node (ref "U1") (pin "31") (pinfunction "STMU0_31") (pintype "passive"))
    )
    (net (code "28") (name "AGND") (class "Default")
      (node (ref "R4") (pin "1") (pinfunction "1_1") (pintype "passive"))
      (node (ref "U2") (pin "21") (pinfunction "AGND2_21") (pintype "power_in"))
      (node (ref "U2") (pin "25") (pinfunction "EXP_25") (pintype "power_in"))
      (node (ref "U2") (pin "9") (pinfunction "AGND1_9") (pintype "power_in"))
    )
    (net (code "29") (name "AVSS") (class "Default")
      (node (ref "C10") (pin "2") (pinfunction "2_2") (pintype "passive"))
      (node (ref "C13") (pin "1") (pinfunction "1_1") (pintype "passive"))
      (node (ref "C14") (pin "2") (pinfunction "2_2") (pintype "passive"))
      (node (ref "C7") (pin "2") (pinfunction "2_2") (pintype "passive"))
      (node (ref "C8") (pin "1") (pinfunction "1_1") (pintype "passive"))
      (node (ref "C9") (pin "2") (pinfunction "2_2") (pintype "passive"))
      (node (ref "R2") (pin "1") (pinfunction "1_1") (pintype "passive"))
      (node (ref "U1") (pin "48") (pinfunction "AVSS_48") (pintype "passive"))
    )
    (net (code "30") (name "DVSS") (class "Default")
      (node (ref "C1") (pin "2") (pinfunction "2_2") (pintype "passive"))
      (node (ref "C11") (pin "2") (pinfunction "2_2") (pintype "passive"))
      (node (ref "C12") (pin "1") (pinfunction "1_1") (pintype "passive"))
      (node (ref "C15") (pin "2") (pinfunction "2_2") (pintype "passive"))
      (node (ref "C16") (pin "2") (pinfunction "2_2") (pintype "passive"))
      (node (ref "C17") (pin "2") (pinfunction "2_2") (pintype "passive"))
      (node (ref "C2") (pin "2") (pinfunction "2_2") (pintype "passive"))
      (node (ref "C3") (pin "2") (pinfunction "2_2") (pintype "passive"))
      (node (ref "C4") (pin "2") (pinfunction "2_2") (pintype "passive"))
      (node (ref "R1") (pin "1") (pinfunction "1_1") (pintype "passive"))
      (node (ref "U1") (pin "16") (pinfunction "vss_dig3_16") (pintype "passive"))
      (node (ref "U1") (pin "18") (pinfunction "dvss_dig3_18") (pintype "passive"))
      (node (ref "U1") (pin "2") (pinfunction "dvss_dig2_2") (pintype "passive"))
      (node (ref "U1") (pin "55") (pinfunction "VSS_55") (pintype "passive"))
      (node (ref "U1") (pin "57") (pinfunction "vss_dig1_57") (pintype "passive"))
      (node (ref "U1") (pin "7") (pinfunction "vss_dig2_7") (pintype "passive"))
    )
    (net (code "31") (name "ENS1_VDD3V3") (class "Default")
      (node (ref "C1") (pin "1") (pinfunction "1_1") (pintype "passive"))
      (node (ref "C16") (pin "1") (pinfunction "1_1") (pintype "passive"))
      (node (ref "C34") (pin "1") (pinfunction "1_1") (pintype "passive"))
      (node (ref "C4") (pin "1") (pinfunction "1_1") (pintype "passive"))
      (node (ref "J1") (pin "4") (pinfunction "4_4") (pintype "passive"))
      (node (ref "U1") (pin "17") (pinfunction "vdd_io3_17") (pintype "passive"))
      (node (ref "U1") (pin "3") (pinfunction "vdd_io1_3") (pintype "passive"))
      (node (ref "U1") (pin "56") (pinfunction "vdd_io2_56") (pintype "passive"))
      (node (ref "U5") (pin "A1") (pinfunction "OUT_A1") (pintype "passive"))
    )
    (net (code "32") (name "ENS1_VDD5V") (class "Default")
      (node (ref "C36") (pin "1") (pinfunction "1_1") (pintype "passive"))
      (node (ref "C7") (pin "1") (pinfunction "1_1") (pintype "passive"))
      (node (ref "C8") (pin "2") (pinfunction "2_2") (pintype "passive"))
      (node (ref "L1") (pin "1") (pinfunction "1_1") (pintype "passive"))
      (node (ref "U1") (pin "49") (pinfunction "VBAT_49") (pintype "passive"))
      (node (ref "U6") (pin "A1") (pinfunction "OUT_A1") (pintype "passive"))
    )
    (net (code "33") (name "GND") (class "Default")
      (node (ref "C18") (pin "2") (pinfunction "2_2") (pintype "passive"))
      (node (ref "C19") (pin "1") (pinfunction "1_1") (pintype "passive"))
      (node (ref "C20") (pin "2") (pinfunction "2_2") (pintype "passive"))
      (node (ref "C21") (pin "1") (pinfunction "1_1") (pintype "passive"))
      (node (ref "C22") (pin "2") (pinfunction "2_2") (pintype "passive"))
      (node (ref "C23") (pin "2") (pinfunction "2_2") (pintype "passive"))
      (node (ref "C24") (pin "2") (pinfunction "2_2") (pintype "passive"))
      (node (ref "C25") (pin "1") (pinfunction "1_1") (pintype "passive"))
      (node (ref "C26") (pin "2") (pinfunction "2_2") (pintype "passive"))
      (node (ref "C27") (pin "2") (pinfunction "2_2") (pintype "passive"))
      (node (ref "C28") (pin "2") (pinfunction "2_2") (pintype "passive"))
      (node (ref "C29") (pin "1") (pinfunction "1_1") (pintype "passive"))
      (node (ref "C30") (pin "2") (pinfunction "2_2") (pintype "passive"))
      (node (ref "C31") (pin "2") (pinfunction "2_2") (pintype "passive"))
      (node (ref "C32") (pin "2") (pinfunction "2_2") (pintype "passive"))
      (node (ref "C33") (pin "2") (pinfunction "2_2") (pintype "passive"))
      (node (ref "C34") (pin "2") (pinfunction "2_2") (pintype "passive"))
      (node (ref "C35") (pin "1") (pinfunction "1_1") (pintype "passive"))
      (node (ref "C36") (pin "2") (pinfunction "2_2") (pintype "passive"))
      (node (ref "C37") (pin "1") (pinfunction "1_1") (pintype "passive"))
      (node (ref "C38") (pin "2") (pinfunction "2_2") (pintype "passive"))
      (node (ref "C39") (pin "2") (pinfunction "2_2") (pintype "passive"))
      (node (ref "C40") (pin "2") (pinfunction "2_2") (pintype "passive"))
      (node (ref "C41") (pin "2") (pinfunction "2_2") (pintype "passive"))
      (node (ref "C42") (pin "1") (pinfunction "1_1") (pintype "passive"))
      (node (ref "D2") (pin "2") (pinfunction "2_2") (pintype "passive"))
      (node (ref "J1") (pin "1") (pinfunction "1_1") (pintype "passive"))
      (node (ref "J10") (pin "0") (pinfunction "0_0") (pintype "passive"))
      (node (ref "J11") (pin "0") (pinfunction "0_0") (pintype "passive"))
      (node (ref "J11") (pin "3") (pinfunction "3_3") (pintype "passive"))
      (node (ref "J2") (pin "1") (pinfunction "1_1") (pintype "passive"))
      (node (ref "J3") (pin "2") (pinfunction "2_2") (pintype "passive"))
      (node (ref "J4") (pin "2") (pinfunction "2_2") (pintype "passive"))
      (node (ref "J7") (pin "11") (pinfunction "11_11") (pintype "passive"))
      (node (ref "J7") (pin "12") (pinfunction "12_12") (pintype "passive"))
      (node (ref "J7") (pin "15") (pinfunction "15_15") (pintype "passive"))
      (node (ref "J8") (pin "11") (pinfunction "11_11") (pintype "passive"))
      (node (ref "J8") (pin "12") (pinfunction "12_12") (pintype "passive"))
      (node (ref "J8") (pin "15") (pinfunction "15_15") (pintype "passive"))
      (node (ref "J9") (pin "11") (pinfunction "11_11") (pintype "passive"))
      (node (ref "J9") (pin "12") (pinfunction "12_12") (pintype "passive"))
      (node (ref "J9") (pin "15") (pinfunction "15_15") (pintype "passive"))
      (node (ref "R1") (pin "2") (pinfunction "2_2") (pintype "passive"))
      (node (ref "R10") (pin "2") (pinfunction "2_2") (pintype "passive"))
      (node (ref "R11") (pin "2") (pinfunction "2_2") (pintype "passive"))
      (node (ref "R13") (pin "1") (pinfunction "1_1") (pintype "passive"))
      (node (ref "R14") (pin "1") (pinfunction "1_1") (pintype "passive"))
      (node (ref "R2") (pin "2") (pinfunction "2_2") (pintype "passive"))
      (node (ref "R3") (pin "2") (pinfunction "2_2") (pintype "passive"))
      (node (ref "R4") (pin "2") (pinfunction "2_2") (pintype "passive"))
      (node (ref "R6") (pin "2") (pinfunction "2_2") (pintype "passive"))
      (node (ref "R9") (pin "1") (pinfunction "1_1") (pintype "passive"))
      (node (ref "U2") (pin "23") (pinfunction "PGND1_23") (pintype "power_in"))
      (node (ref "U2") (pin "24") (pinfunction "PGND2_24") (pintype "power_in"))
      (node (ref "U3") (pin "B2") (pinfunction "VSS_B2") (pintype "passive"))
      (node (ref "U4") (pin "1") (pinfunction "GND_1") (pintype "passive"))
      (node (ref "U4") (pin "7") (pinfunction "PP_7") (pintype "passive"))
      (node (ref "U5") (pin "B1") (pinfunction "GND_B1") (pintype "passive"))
      (node (ref "U6") (pin "B1") (pinfunction "GND_B1") (pintype "passive"))
      (node (ref "U7") (pin "6") (pinfunction "GND_6") (pintype "passive"))
      (node (ref "U8") (pin "2") (pinfunction "GND_2") (pintype "passive"))
      (node (ref "U9") (pin "A1") (pinfunction "GND_A1") (pintype "passive"))
    )
    (net (code "34") (name "HVSS") (class "Default")
      (node (ref "C5") (pin "2") (pinfunction "2_2") (pintype "passive"))
      (node (ref "C6") (pin "2") (pinfunction "2_2") (pintype "passive"))
      (node (ref "R3") (pin "1") (pinfunction "1_1") (pintype "passive"))
      (node (ref "U1") (pin "65") (pinfunction "HVSS_65") (pintype "passive"))
    )
    (net (code "35") (name "Net-(U1-AVDD)") (class "Default")
      (node (ref "C10") (pin "1") (pinfunction "1_1") (pintype "passive"))
      (node (ref "U1") (pin "51") (pinfunction "AVDD_51") (pintype "passive"))
    )
    (net (code "36") (name "Net-(U1-AVDD5P0)") (class "Default")
      (node (ref "C9") (pin "1") (pinfunction "1_1") (pintype "passive"))
      (node (ref "U1") (pin "50") (pinfunction "AVDD5P0_50") (pintype "passive"))
    )
    (net (code "37") (name "Net-(U1-VSYS_LDO)") (class "Default")
      (node (ref "C13") (pin "2") (pinfunction "2_2") (pintype "passive"))
      (node (ref "C14") (pin "1") (pinfunction "1_1") (pintype "passive"))
      (node (ref "U1") (pin "53") (pinfunction "VSYS_LDO_53") (pintype "passive"))
    )
    (net (code "38") (name "Net-(U2-ASYS)") (class "Default")
      (node (ref "C23") (pin "1") (pinfunction "1_1") (pintype "passive"))
      (node (ref "C24") (pin "1") (pinfunction "1_1") (pintype "passive"))
      (node (ref "C25") (pin "2") (pinfunction "2_2") (pintype "passive"))
      (node (ref "U2") (pin "17") (pinfunction "ASYS_17") (pintype "power_in"))
      (node (ref "U2") (pin "2") (pinfunction "PSYS2_2") (pintype "power_in"))
      (node (ref "U2") (pin "20") (pinfunction "PSYS1_20") (pintype "power_in"))
    )
    (net (code "39") (name "Net-(U2-LDO1_OUT)") (class "Default")
      (node (ref "C26") (pin "1") (pinfunction "1_1") (pintype "passive"))
      (node (ref "U2") (pin "12") (pinfunction "LDO1_OUT_12") (pintype "power_in"))
    )
    (net (code "40") (name "Net-(U2-LX1)") (class "Default")
      (node (ref "L2") (pin "1") (pinfunction "1_1") (pintype "passive"))
      (node (ref "U2") (pin "22") (pinfunction "LX1_22") (pintype "power_in"))
    )
    (net (code "41") (name "Net-(U2-LX2)") (class "Default")
      (node (ref "L3") (pin "1") (pinfunction "1_1") (pintype "passive"))
      (node (ref "U2") (pin "1") (pinfunction "LX2_1") (pintype "power_in"))
    )
    (net (code "42") (name "Net-(U3-BIN)") (class "Default")
      (node (ref "R6") (pin "1") (pinfunction "1_1") (pintype "passive"))
      (node (ref "U3") (pin "B1") (pinfunction "BIN_B1") (pintype "passive"))
    )
    (net (code "43") (name "Net-(U3-VDD)") (class "Default")
      (node (ref "C30") (pin "1") (pinfunction "1_1") (pintype "passive"))
      (node (ref "U3") (pin "B3") (pinfunction "VDD_B3") (pintype "passive"))
    )
    (net (code "44") (name "Net-(U4-L)") (class "Default")
      (node (ref "L4") (pin "2") (pinfunction "2_2") (pintype "passive"))
      (node (ref "U4") (pin "5") (pinfunction "L_5") (pintype "passive"))
    )
    (net (code "45") (name "Net-(U7-NC1)") (class "Default")
      (node (ref "R10") (pin "1") (pinfunction "1_1") (pintype "passive"))
      (node (ref "U7") (pin "5") (pinfunction "NC1_5") (pintype "passive"))
    )
    (net (code "46") (name "Net-(U7-NC2)") (class "Default")
      (node (ref "R11") (pin "1") (pinfunction "1_1") (pintype "passive"))
      (node (ref "U7") (pin "7") (pinfunction "NC2_7") (pintype "passive"))
    )
    (net (code "47") (name "Net-(U8-FB)") (class "Default")
      (node (ref "R12") (pin "1") (pinfunction "1_1") (pintype "passive"))
      (node (ref "R13") (pin "2") (pinfunction "2_2") (pintype "passive"))
      (node (ref "U8") (pin "4") (pinfunction "FB_4") (pintype "passive"))
    )
    (net (code "48") (name "Net-(U9-SW)") (class "Default")
      (node (ref "L5") (pin "2") (pinfunction "2_2") (pintype "passive"))
      (node (ref "U9") (pin "B2") (pinfunction "SW_B2") (pintype "passive"))
    )
    (net (code "49") (name "Net-(U9-VSET)") (class "Default")
      (node (ref "R14") (pin "2") (pinfunction "2_2") (pintype "passive"))
      (node (ref "U9") (pin "C2") (pinfunction "VSET_C2") (pintype "passive"))
    )
    (net (code "50") (name "SW1_VDD1V8") (class "Default")
      (node (ref "C28") (pin "1") (pinfunction "1_1") (pintype "passive"))
      (node (ref "J7") (pin "13") (pinfunction "13_13") (pintype "passive"))
      (node (ref "J7") (pin "14") (pinfunction "14_14") (pintype "passive"))
      (node (ref "J7") (pin "16") (pinfunction "16_16") (pintype "passive"))
      (node (ref "J9") (pin "9") (pinfunction "9_9") (pintype "passive"))
      (node (ref "L2") (pin "2") (pinfunction "2_2") (pintype "passive"))
      (node (ref "U2") (pin "19") (pinfunction "SW1_OUT_19") (pintype "input"))
    )
    (net (code "51") (name "SW2_VDD3V3") (class "Default")
      (node (ref "C29") (pin "2") (pinfunction "2_2") (pintype "passive"))
      (node (ref "C33") (pin "1") (pinfunction "1_1") (pintype "passive"))
      (node (ref "C35") (pin "2") (pinfunction "2_2") (pintype "passive"))
      (node (ref "C38") (pin "1") (pinfunction "1_1") (pintype "passive"))
      (node (ref "J8") (pin "13") (pinfunction "13_13") (pintype "passive"))
      (node (ref "J8") (pin "14") (pinfunction "14_14") (pintype "passive"))
      (node (ref "J8") (pin "16") (pinfunction "16_16") (pintype "passive"))
      (node (ref "J9") (pin "10") (pinfunction "10_10") (pintype "passive"))
      (node (ref "L3") (pin "2") (pinfunction "2_2") (pintype "passive"))
      (node (ref "L4") (pin "1") (pinfunction "1_1") (pintype "passive"))
      (node (ref "U2") (pin "3") (pinfunction "SW2_OUT_3") (pintype "input"))
      (node (ref "U4") (pin "6") (pinfunction "VIN_6") (pintype "passive"))
      (node (ref "U5") (pin "A2") (pinfunction "IN_A2") (pintype "passive"))
      (node (ref "U7") (pin "1") (pinfunction "VCC_1") (pintype "passive"))
    )
    (net (code "52") (name "VBAT") (class "Default")
      (node (ref "C31") (pin "1") (pinfunction "1_1") (pintype "passive"))
      (node (ref "J3") (pin "1") (pinfunction "1_1") (pintype "passive"))
      (node (ref "R8") (pin "2") (pinfunction "2_2") (pintype "passive"))
      (node (ref "U3") (pin "C1") (pinfunction "SRP_C1") (pintype "passive"))
      (node (ref "U3") (pin "C3") (pinfunction "BAT_C3") (pintype "passive"))
    )
    (net (code "53") (name "VBAT_VSYS") (class "Default")
      (node (ref "C21") (pin "2") (pinfunction "2_2") (pintype "passive"))
      (node (ref "C22") (pin "1") (pinfunction "1_1") (pintype "passive"))
      (node (ref "R8") (pin "1") (pinfunction "1_1") (pintype "passive"))
      (node (ref "U2") (pin "13") (pinfunction "VBAT_BKUP_13") (pintype "power_in"))
      (node (ref "U2") (pin "18") (pinfunction "VBAT_18") (pintype "power_in"))
      (node (ref "U3") (pin "C2") (pinfunction "SRN_C2") (pintype "passive"))
    )
    (net (code "54") (name "VCC_1V8") (class "Default")
      (node (ref "C40") (pin "1") (pinfunction "1_1") (pintype "passive"))
      (node (ref "J8") (pin "6") (pinfunction "6_6") (pintype "passive"))
      (node (ref "R12") (pin "2") (pinfunction "2_2") (pintype "passive"))
      (node (ref "U8") (pin "5") (pinfunction "OUT_5") (pintype "passive"))
    )
    (net (code "55") (name "VCC_3V3") (class "Default")
      (node (ref "C27") (pin "1") (pinfunction "1_1") (pintype "passive"))
      (node (ref "C39") (pin "1") (pinfunction "1_1") (pintype "passive"))
      (node (ref "C41") (pin "1") (pinfunction "1_1") (pintype "passive"))
      (node (ref "U2") (pin "15") (pinfunction "LDO2_OUT_15") (pintype "power_in"))
      (node (ref "U8") (pin "1") (pinfunction "IN_1") (pintype "passive"))
      (node (ref "U8") (pin "3") (pinfunction "EN_3") (pintype "passive"))
      (node (ref "U9") (pin "B1") (pinfunction "VIN_B1") (pintype "passive"))
      (node (ref "U9") (pin "C1") (pinfunction "EN_C1") (pintype "passive"))
    )
    (net (code "56") (name "VDD_1V9") (class "Default")
      (node (ref "C42") (pin "2") (pinfunction "2_2") (pintype "passive"))
      (node (ref "J8") (pin "4") (pinfunction "4_4") (pintype "passive"))
      (node (ref "J8") (pin "5") (pinfunction "5_5") (pintype "passive"))
      (node (ref "J9") (pin "8") (pinfunction "8_8") (pintype "passive"))
      (node (ref "L5") (pin "1") (pinfunction "1_1") (pintype "passive"))
      (node (ref "R5") (pin "2") (pinfunction "2_2") (pintype "passive"))
      (node (ref "R7") (pin "2") (pinfunction "2_2") (pintype "passive"))
      (node (ref "U9") (pin "A2") (pinfunction "VOS_A2") (pintype "passive"))
    )
    (net (code "57") (name "VDD_5V") (class "Default")
      (node (ref "C32") (pin "1") (pinfunction "1_1") (pintype "passive"))
      (node (ref "C37") (pin "2") (pinfunction "2_2") (pintype "passive"))
      (node (ref "J9") (pin "13") (pinfunction "13_13") (pintype "passive"))
      (node (ref "J9") (pin "14") (pinfunction "14_14") (pintype "passive"))
      (node (ref "J9") (pin "16") (pinfunction "16_16") (pintype "passive"))
      (node (ref "U4") (pin "2") (pinfunction "VOUT_2") (pintype "passive"))
      (node (ref "U4") (pin "3") (pinfunction "FB_3") (pintype "passive"))
      (node (ref "U6") (pin "A2") (pinfunction "IN_A2") (pintype "passive"))
    )
    (net (code "58") (name "V_CHG_IN") (class "Default")
      (node (ref "C18") (pin "1") (pinfunction "1_1") (pintype "passive"))
      (node (ref "C19") (pin "2") (pinfunction "2_2") (pintype "passive"))
      (node (ref "C20") (pin "1") (pinfunction "1_1") (pintype "passive"))
      (node (ref "D2") (pin "1") (pinfunction "1_1") (pintype "passive"))
      (node (ref "J4") (pin "1") (pinfunction "1_1") (pintype "passive"))
      (node (ref "U2") (pin "16") (pinfunction "VIN_16") (pintype "power_in"))
    )
    (net (code "59") (name "unconnected-(J10-Pad1)") (class "Default")
      (node (ref "J10") (pin "1") (pinfunction "1_1") (pintype "passive+no_connect"))
    )
    (net (code "60") (name "unconnected-(J10-Pad2)") (class "Default")
      (node (ref "J10") (pin "2") (pinfunction "2_2") (pintype "passive+no_connect"))
    )
    (net (code "61") (name "unconnected-(J10-Pad3)") (class "Default")
      (node (ref "J10") (pin "3") (pinfunction "3_3") (pintype "passive+no_connect"))
    )
    (net (code "62") (name "unconnected-(J10-Pad4)") (class "Default")
      (node (ref "J10") (pin "4") (pinfunction "4_4") (pintype "passive+no_connect"))
    )
    (net (code "63") (name "unconnected-(J10-Pad7)") (class "Default")
      (node (ref "J10") (pin "7") (pinfunction "7_7") (pintype "passive+no_connect"))
    )
    (net (code "64") (name "unconnected-(J10-Pad8)") (class "Default")
      (node (ref "J10") (pin "8") (pinfunction "8_8") (pintype "passive+no_connect"))
    )
    (net (code "65") (name "unconnected-(J11-Pad1)") (class "Default")
      (node (ref "J11") (pin "1") (pinfunction "1_1") (pintype "passive+no_connect"))
    )
    (net (code "66") (name "unconnected-(J11-Pad4)") (class "Default")
      (node (ref "J11") (pin "4") (pinfunction "4_4") (pintype "passive+no_connect"))
    )
    (net (code "67") (name "unconnected-(J11-Pad7)") (class "Default")
      (node (ref "J11") (pin "7") (pinfunction "7_7") (pintype "passive+no_connect"))
    )
    (net (code "68") (name "unconnected-(J11-Pad8)") (class "Default")
      (node (ref "J11") (pin "8") (pinfunction "8_8") (pintype "passive+no_connect"))
    )
    (net (code "69") (name "unconnected-(U1-STMU2-Pad29)") (class "Default")
      (node (ref "U1") (pin "29") (pinfunction "STMU2_29") (pintype "passive+no_connect"))
    )
    (net (code "70") (name "unconnected-(U1-STMU3-Pad28)") (class "Default")
      (node (ref "U1") (pin "28") (pinfunction "STMU3_28") (pintype "passive+no_connect"))
    )
    (net (code "71") (name "unconnected-(U1-boot0-Pad20)") (class "Default")
      (node (ref "U1") (pin "20") (pinfunction "boot0_20") (pintype "passive+no_connect"))
    )
    (net (code "72") (name "unconnected-(U1-boot1-Pad19)") (class "Default")
      (node (ref "U1") (pin "19") (pinfunction "boot1_19") (pintype "passive+no_connect"))
    )
    (net (code "73") (name "unconnected-(U1-gpio5-Pad61)") (class "Default")
      (node (ref "U1") (pin "61") (pinfunction "gpio5_61") (pintype "passive+no_connect"))
    )
    (net (code "74") (name "unconnected-(U1-gpio8-Pad62)") (class "Default")
      (node (ref "U1") (pin "62") (pinfunction "gpio8_62") (pintype "passive+no_connect"))
    )
    (net (code "75") (name "unconnected-(U1-gpio9-Pad63)") (class "Default")
      (node (ref "U1") (pin "63") (pinfunction "gpio9_63") (pintype "passive+no_connect"))
    )
    (net (code "76") (name "unconnected-(U1-gpio10-Pad64)") (class "Default")
      (node (ref "U1") (pin "64") (pinfunction "gpio10_64") (pintype "passive+no_connect"))
    )
    (net (code "77") (name "unconnected-(U1-gpio11-Pad1)") (class "Default")
      (node (ref "U1") (pin "1") (pinfunction "gpio11_1") (pintype "passive+no_connect"))
    )
    (net (code "78") (name "unconnected-(U1-gpio14-Pad10)") (class "Default")
      (node (ref "U1") (pin "10") (pinfunction "gpio14_10") (pintype "passive+no_connect"))
    )
    (net (code "79") (name "unconnected-(U1-gpio15-Pad11)") (class "Default")
      (node (ref "U1") (pin "11") (pinfunction "gpio15_11") (pintype "passive+no_connect"))
    )
    (net (code "80") (name "unconnected-(U1-gpio16-Pad12)") (class "Default")
      (node (ref "U1") (pin "12") (pinfunction "gpio16_12") (pintype "passive+no_connect"))
    )
    (net (code "81") (name "unconnected-(U1-gpio17-Pad13)") (class "Default")
      (node (ref "U1") (pin "13") (pinfunction "gpio17_13") (pintype "passive+no_connect"))
    )
    (net (code "82") (name "unconnected-(U1-gpio18-Pad14)") (class "Default")
      (node (ref "U1") (pin "14") (pinfunction "gpio18_14") (pintype "passive+no_connect"))
    )
    (net (code "83") (name "unconnected-(U1-gpio19-Pad25)") (class "Default")
      (node (ref "U1") (pin "25") (pinfunction "gpio19_25") (pintype "passive+no_connect"))
    )
    (net (code "84") (name "unconnected-(U1-gpio20-Pad24)") (class "Default")
      (node (ref "U1") (pin "24") (pinfunction "gpio20_24") (pintype "passive+no_connect"))
    )
    (net (code "85") (name "unconnected-(U1-gpio21-Pad23)") (class "Default")
      (node (ref "U1") (pin "23") (pinfunction "gpio21_23") (pintype "passive+no_connect"))
    )
    (net (code "86") (name "unconnected-(U1-gpio22-Pad22)") (class "Default")
      (node (ref "U1") (pin "22") (pinfunction "gpio22_22") (pintype "passive+no_connect"))
    )
    (net (code "87") (name "unconnected-(U1-ise_invinpad-Pad6)") (class "Default")
      (node (ref "U1") (pin "6") (pinfunction "ise_invinpad_6") (pintype "passive+no_connect"))
    )
    (net (code "88") (name "unconnected-(U1-ise_invoutpad-Pad5)") (class "Default")
      (node (ref "U1") (pin "5") (pinfunction "ise_invoutpad_5") (pintype "passive+no_connect"))
    )
    (net (code "89") (name "unconnected-(U2-MODESEL0-Pad7)") (class "Default")
      (node (ref "U2") (pin "7") (pinfunction "MODESEL0_7") (pintype "input+no_connect"))
    )
    (net (code "90") (name "unconnected-(U2-MODESEL1-Pad8)") (class "Default")
      (node (ref "U2") (pin "8") (pinfunction "MODESEL1_8") (pintype "input+no_connect"))
    )
    (net (code "91") (name "unconnected-(U2-SYSRSTN-Pad11)") (class "Default")
      (node (ref "U2") (pin "11") (pinfunction "SYSRSTN_11") (pintype "output+no_connect"))
    )
    (net (code "92") (name "unconnected-(U2-TS-Pad14)") (class "Default")
      (node (ref "U2") (pin "14") (pinfunction "TS_14") (pintype "input+no_connect"))
    )
  )
)
